# Ultra-Mega-PS-DAC-V1_00.net
KiCad netlist of a schematic drawn in Altium Designer
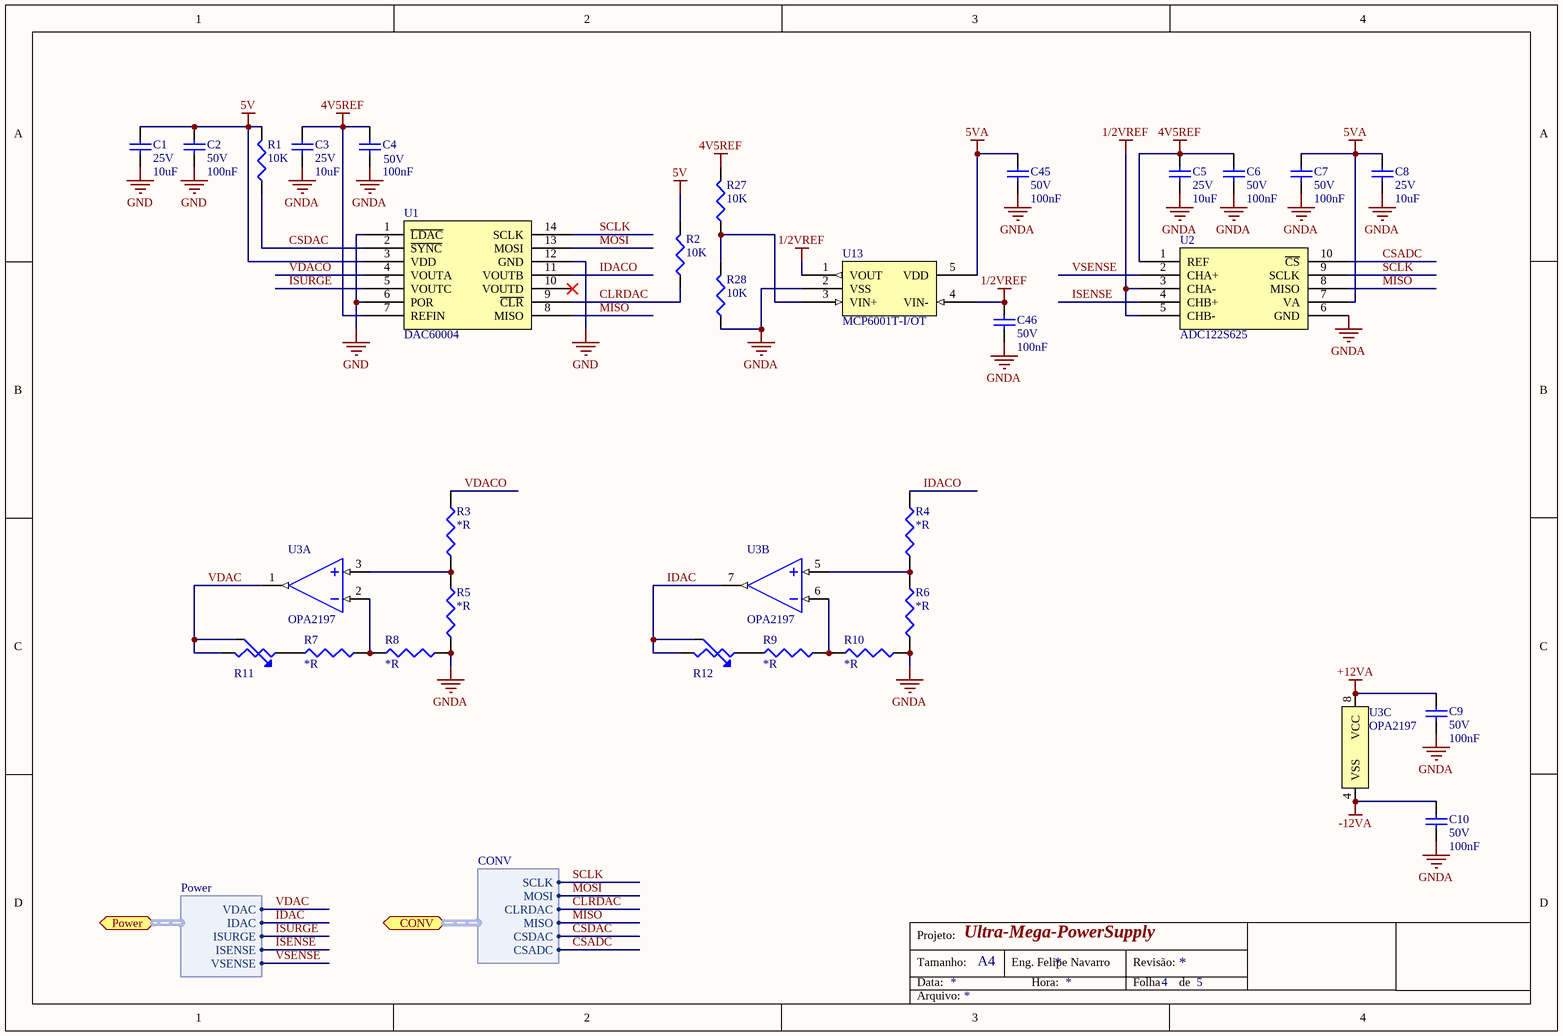
[diagram p0: Ultra-Mega-PS-DAC-V1.00.SchDoc]

(export (version "E")
  (design (tool "Eeschema 10.0.6"))
  (components
    (comp (ref "C1")
      (value "10uF")
      (footprint "CC0805")
      (description "Capacitor (Semiconductor SIM Model)")
      (fields (field (name "TENSÃO") "25V") (field (name "Comment") "Capacitor Cerâmico"))
      (libsource (lib "NavarroCAP") (part "Cap 10uF 25V 0805 X5R"))
    )
    (comp (ref "C2")
      (value "100nF")
      (footprint "CC0603")
      (description "Capacitor (Semiconductor SIM Model)")
      (fields (field (name "TENSÃO") "50V") (field (name "Comment") "Capacitor Cerâmico"))
      (libsource (lib "NavarroCAP") (part "Cap 100nF 50V 0603 X7R"))
    )
    (comp (ref "C3")
      (value "10uF")
      (footprint "CC0805")
      (description "Capacitor (Semiconductor SIM Model)")
      (fields (field (name "TENSÃO") "25V") (field (name "Comment") "Capacitor Cerâmico"))
      (libsource (lib "NavarroCAP") (part "Cap 10uF 25V 0805 X5R"))
    )
    (comp (ref "C4")
      (value "100nF")
      (footprint "CC0603")
      (description "Capacitor (Semiconductor SIM Model)")
      (fields (field (name "TENSÃO") "50V") (field (name "Comment") "Capacitor Cerâmico"))
      (libsource (lib "NavarroCAP") (part "Cap 100nF 50V 0603 X7R"))
    )
    (comp (ref "C5")
      (value "10uF")
      (footprint "CC0805")
      (description "Capacitor (Semiconductor SIM Model)")
      (fields (field (name "TENSÃO") "25V") (field (name "Comment") "Capacitor Cerâmico"))
      (libsource (lib "NavarroCAP") (part "Cap 10uF 25V 0805 X5R"))
    )
    (comp (ref "C6")
      (value "100nF")
      (footprint "CC0603")
      (description "Capacitor (Semiconductor SIM Model)")
      (fields (field (name "TENSÃO") "50V") (field (name "Comment") "Capacitor Cerâmico"))
      (libsource (lib "NavarroCAP") (part "Cap 100nF 50V 0603 X7R"))
    )
    (comp (ref "C7")
      (value "100nF")
      (footprint "CC0603")
      (description "Capacitor (Semiconductor SIM Model)")
      (fields (field (name "TENSÃO") "50V") (field (name "Comment") "Capacitor Cerâmico"))
      (libsource (lib "NavarroCAP") (part "Cap 100nF 50V 0603 X7R"))
    )
    (comp (ref "C8")
      (value "10uF")
      (footprint "CC0805")
      (description "Capacitor (Semiconductor SIM Model)")
      (fields (field (name "TENSÃO") "25V") (field (name "Comment") "Capacitor Cerâmico"))
      (libsource (lib "NavarroCAP") (part "Cap 10uF 25V 0805 X5R"))
    )
    (comp (ref "C9")
      (value "100nF")
      (footprint "CC0603")
      (description "Capacitor (Semiconductor SIM Model)")
      (fields (field (name "TENSÃO") "50V") (field (name "Comment") "Capacitor Cerâmico"))
      (libsource (lib "NavarroCAP") (part "Cap 100nF 50V 0603 X7R"))
    )
    (comp (ref "C10")
      (value "100nF")
      (footprint "CC0603")
      (description "Capacitor (Semiconductor SIM Model)")
      (fields (field (name "TENSÃO") "50V") (field (name "Comment") "Capacitor Cerâmico"))
      (libsource (lib "NavarroCAP") (part "Cap 100nF 50V 0603 X7R"))
    )
    (comp (ref "C45")
      (value "100nF")
      (footprint "CC0603")
      (description "Capacitor (Semiconductor SIM Model)")
      (fields (field (name "TENSÃO") "50V") (field (name "Comment") "Capacitor Cerâmico"))
      (libsource (lib "NavarroCAP") (part "Cap 100nF 50V 0603 X7R"))
    )
    (comp (ref "C46")
      (value "100nF")
      (footprint "CC0603")
      (description "Capacitor (Semiconductor SIM Model)")
      (fields (field (name "TENSÃO") "50V") (field (name "Comment") "Capacitor Cerâmico"))
      (libsource (lib "NavarroCAP") (part "Cap 100nF 50V 0603 X7R"))
    )
    (comp (ref "R1")
      (value "10K")
      (footprint "CC0603")
      (description "Resistor")
      (libsource (lib "NavarroRES") (part "Res 10K 1% 0603 1/10W"))
    )
    (comp (ref "R2")
      (value "10K")
      (footprint "CC0603")
      (description "Resistor")
      (libsource (lib "NavarroRES") (part "Res 10K 1% 0603 1/10W"))
    )
    (comp (ref "R3")
      (value "*R")
      (footprint "CC0603")
      (description "Resistor")
      (libsource (lib "NavarroRES") (part "Res - $Val $% $Footprint $Pot"))
    )
    (comp (ref "R4")
      (value "*R")
      (footprint "CC0603")
      (description "Resistor")
      (libsource (lib "NavarroRES") (part "Res - $Val $% $Footprint $Pot"))
    )
    (comp (ref "R5")
      (value "*R")
      (footprint "CC0603")
      (description "Resistor")
      (libsource (lib "NavarroRES") (part "Res - $Val $% $Footprint $Pot"))
    )
    (comp (ref "R6")
      (value "*R")
      (footprint "CC0603")
      (description "Resistor")
      (libsource (lib "NavarroRES") (part "Res - $Val $% $Footprint $Pot"))
    )
    (comp (ref "R7")
      (value "*R")
      (footprint "CC0603")
      (description "Resistor")
      (libsource (lib "NavarroRES") (part "Res - $Val $% $Footprint $Pot"))
    )
    (comp (ref "R8")
      (value "*R")
      (footprint "CC0603")
      (description "Resistor")
      (libsource (lib "NavarroRES") (part "Res - $Val $% $Footprint $Pot"))
    )
    (comp (ref "R9")
      (value "*R")
      (footprint "CC0603")
      (description "Resistor")
      (libsource (lib "NavarroRES") (part "Res - $Val $% $Footprint $Pot"))
    )
    (comp (ref "R10")
      (value "*R")
      (footprint "CC0603")
      (description "Resistor")
      (libsource (lib "NavarroRES") (part "Res - $Val $% $Footprint $Pot"))
    )
    (comp (ref "R11")
      (value "Potenciômetro")
      (footprint "POT")
      (description "Trimmer")
      (libsource (lib "NavarroRES") (part "Res Trim"))
    )
    (comp (ref "R12")
      (value "Potenciômetro")
      (footprint "POT")
      (description "Trimmer")
      (libsource (lib "NavarroRES") (part "Res Trim"))
    )
    (comp (ref "R27")
      (value "10K")
      (footprint "CC0603")
      (description "Resistor")
      (libsource (lib "NavarroRES") (part "Res 10K 1% 0603 1/10W"))
    )
    (comp (ref "R28")
      (value "10K")
      (footprint "CC0603")
      (description "Resistor")
      (libsource (lib "NavarroRES") (part "Res 10K 1% 0603 1/10W"))
    )
    (comp (ref "U1")
      (value "DAC60004")
      (footprint "TSSOP-14N")
      (description "DACx0004, Quad 16-,14-,12-Bit, 1 LSB INL, Buffered, Voltage-Output Digital-to-Analog  Converters")
      (libsource (lib "Navarro") (part "DAC6004"))
    )
    (comp (ref "U2")
      (value "ADC122S625")
      (footprint "MSOP10")
      (description "ADC122S625 Dual 12-Bit, 50 kSPS to 200 kSPS, Simultaneous Sampling A/D Converter")
      (libsource (lib "Navarro") (part "ADC122S625"))
    )
    (comp (ref "U3")
      (value "OPA2197")
      (footprint "SOIC-8N")
      (description "OPAx197 36-V, Precision, Rail-to-Rail Input/Output, Low Offset Voltage, Operational Amplifiers")
      (libsource (lib "") (part "OPA2197_1"))
    )
    (comp (ref "U13")
      (value "MCP6001T-I/OT")
      (footprint "SOT-23-5N")
      (description "1 MHz, Low-Power Op Amp")
      (libsource (lib "Navarro") (part "MCP6001"))
    )
  )
  (nets
    (net (code "3") (name "+12VA") (class "Default")
      (node (ref "C9") (pin "2") (pinfunction "2_2") (pintype "passive"))
      (node (ref "U3") (pin "8") (pinfunction "VCC_8") (pintype "power_in"))
    )
    (net (code "4") (name "-12VA") (class "Default")
      (node (ref "C10") (pin "2") (pinfunction "2_2") (pintype "passive"))
      (node (ref "U3") (pin "4") (pinfunction "VSS_4") (pintype "power_in"))
    )
    (net (code "5") (name "/CLRDAC") (class "Default")
      (node (ref "R2") (pin "1") (pinfunction "1_1") (pintype "passive"))
      (node (ref "U1") (pin "9") (pinfunction "~{CLR}_9") (pintype "passive"))
    )
    (net (code "6") (name "/CSADC") (class "Default")
      (node (ref "U2") (pin "10") (pinfunction "~{CS}_10") (pintype "passive"))
    )
    (net (code "7") (name "/CSDAC") (class "Default")
      (node (ref "R1") (pin "1") (pinfunction "1_1") (pintype "passive"))
      (node (ref "U1") (pin "2") (pinfunction "~{SYNC}_2") (pintype "passive"))
    )
    (net (code "8") (name "/IDAC") (class "Default")
      (node (ref "R12") (pin "2") (pinfunction "TAP_2") (pintype "passive"))
      (node (ref "R12") (pin "3") (pinfunction "3_3") (pintype "passive"))
      (node (ref "U3") (pin "7") (pinfunction "OUTB_7") (pintype "output"))
    )
    (net (code "9") (name "/IDACO") (class "Default")
      (node (ref "R4") (pin "2") (pinfunction "2_2") (pintype "passive"))
      (node (ref "U1") (pin "11") (pinfunction "VOUTB_11") (pintype "passive"))
    )
    (net (code "10") (name "/ISENSE") (class "Default")
      (node (ref "U2") (pin "4") (pinfunction "CHB+_4") (pintype "power_in"))
    )
    (net (code "11") (name "/ISURGE") (class "Default")
      (node (ref "U1") (pin "5") (pinfunction "VOUTC_5") (pintype "passive"))
    )
    (net (code "12") (name "/MISO") (class "Default")
      (node (ref "U1") (pin "8") (pinfunction "MISO_8") (pintype "passive"))
      (node (ref "U2") (pin "8") (pinfunction "MISO_8") (pintype "passive"))
    )
    (net (code "13") (name "/MOSI") (class "Default")
      (node (ref "U1") (pin "13") (pinfunction "MOSI_13") (pintype "passive"))
    )
    (net (code "14") (name "/SCLK") (class "Default")
      (node (ref "U1") (pin "14") (pinfunction "SCLK_14") (pintype "passive"))
      (node (ref "U2") (pin "9") (pinfunction "SCLK_9") (pintype "passive"))
    )
    (net (code "15") (name "/VDAC") (class "Default")
      (node (ref "R11") (pin "2") (pinfunction "TAP_2") (pintype "passive"))
      (node (ref "R11") (pin "3") (pinfunction "3_3") (pintype "passive"))
      (node (ref "U3") (pin "1") (pinfunction "OUTA_1") (pintype "output"))
    )
    (net (code "16") (name "/VDACO") (class "Default")
      (node (ref "R3") (pin "2") (pinfunction "2_2") (pintype "passive"))
      (node (ref "U1") (pin "4") (pinfunction "VOUTA_4") (pintype "passive"))
    )
    (net (code "17") (name "/VSENSE") (class "Default")
      (node (ref "U2") (pin "2") (pinfunction "CHA+_2") (pintype "passive"))
    )
    (net (code "20") (name "1{slash}2VREF") (class "Default")
      (node (ref "C46") (pin "2") (pinfunction "2_2") (pintype "passive"))
      (node (ref "U13") (pin "1") (pinfunction "VOUT_1") (pintype "output"))
      (node (ref "U13") (pin "4") (pinfunction "VIN-_4") (pintype "input"))
      (node (ref "U2") (pin "3") (pinfunction "CHA-_3") (pintype "passive"))
      (node (ref "U2") (pin "5") (pinfunction "CHB-_5") (pintype "power_in"))
    )
    (net (code "21") (name "4V5REF") (class "Default")
      (node (ref "C3") (pin "2") (pinfunction "2_2") (pintype "passive"))
      (node (ref "C4") (pin "2") (pinfunction "2_2") (pintype "passive"))
      (node (ref "C5") (pin "2") (pinfunction "2_2") (pintype "passive"))
      (node (ref "C6") (pin "2") (pinfunction "2_2") (pintype "passive"))
      (node (ref "R27") (pin "2") (pinfunction "2_2") (pintype "passive"))
      (node (ref "U1") (pin "7") (pinfunction "REFIN_7") (pintype "passive"))
      (node (ref "U2") (pin "1") (pinfunction "REF_1") (pintype "passive"))
    )
    (net (code "22") (name "5V") (class "Default")
      (node (ref "C1") (pin "2") (pinfunction "2_2") (pintype "passive"))
      (node (ref "C2") (pin "2") (pinfunction "2_2") (pintype "passive"))
      (node (ref "R1") (pin "2") (pinfunction "2_2") (pintype "passive"))
      (node (ref "R2") (pin "2") (pinfunction "2_2") (pintype "passive"))
      (node (ref "U1") (pin "3") (pinfunction "VDD_3") (pintype "power_in"))
    )
    (net (code "23") (name "5VA") (class "Default")
      (node (ref "C45") (pin "2") (pinfunction "2_2") (pintype "passive"))
      (node (ref "C7") (pin "2") (pinfunction "2_2") (pintype "passive"))
      (node (ref "C8") (pin "2") (pinfunction "2_2") (pintype "passive"))
      (node (ref "U13") (pin "5") (pinfunction "VDD_5") (pintype "power_in"))
      (node (ref "U2") (pin "7") (pinfunction "VA_7") (pintype "passive"))
    )
    (net (code "24") (name "GND") (class "Default")
      (node (ref "C1") (pin "1") (pinfunction "1_1") (pintype "passive"))
      (node (ref "C2") (pin "1") (pinfunction "1_1") (pintype "passive"))
      (node (ref "U1") (pin "1") (pinfunction "~{LDAC}_1") (pintype "passive"))
      (node (ref "U1") (pin "12") (pinfunction "GND_12") (pintype "power_in"))
      (node (ref "U1") (pin "6") (pinfunction "POR_6") (pintype "passive"))
    )
    (net (code "25") (name "GNDA") (class "Default")
      (node (ref "C10") (pin "1") (pinfunction "1_1") (pintype "passive"))
      (node (ref "C3") (pin "1") (pinfunction "1_1") (pintype "passive"))
      (node (ref "C4") (pin "1") (pinfunction "1_1") (pintype "passive"))
      (node (ref "C45") (pin "1") (pinfunction "1_1") (pintype "passive"))
      (node (ref "C46") (pin "1") (pinfunction "1_1") (pintype "passive"))
      (node (ref "C5") (pin "1") (pinfunction "1_1") (pintype "passive"))
      (node (ref "C6") (pin "1") (pinfunction "1_1") (pintype "passive"))
      (node (ref "C7") (pin "1") (pinfunction "1_1") (pintype "passive"))
      (node (ref "C8") (pin "1") (pinfunction "1_1") (pintype "passive"))
      (node (ref "C9") (pin "1") (pinfunction "1_1") (pintype "passive"))
      (node (ref "R10") (pin "2") (pinfunction "2_2") (pintype "passive"))
      (node (ref "R28") (pin "1") (pinfunction "1_1") (pintype "passive"))
      (node (ref "R5") (pin "1") (pinfunction "1_1") (pintype "passive"))
      (node (ref "R6") (pin "1") (pinfunction "1_1") (pintype "passive"))
      (node (ref "R8") (pin "2") (pinfunction "2_2") (pintype "passive"))
      (node (ref "U13") (pin "2") (pinfunction "VSS_2") (pintype "power_in"))
      (node (ref "U2") (pin "6") (pinfunction "GND_6") (pintype "passive"))
    )
    (net (code "26") (name "Net-(R11-Pad1)") (class "Default")
      (node (ref "R11") (pin "1") (pinfunction "1_1") (pintype "passive"))
      (node (ref "R7") (pin "1") (pinfunction "1_1") (pintype "passive"))
    )
    (net (code "27") (name "Net-(R12-Pad1)") (class "Default")
      (node (ref "R12") (pin "1") (pinfunction "1_1") (pintype "passive"))
      (node (ref "R9") (pin "1") (pinfunction "1_1") (pintype "passive"))
    )
    (net (code "28") (name "Net-(U3A-INA+)") (class "Default")
      (node (ref "R3") (pin "1") (pinfunction "1_1") (pintype "passive"))
      (node (ref "R5") (pin "2") (pinfunction "2_2") (pintype "passive"))
      (node (ref "U3") (pin "3") (pinfunction "INA+_3") (pintype "input"))
    )
    (net (code "29") (name "Net-(U3A-INA-)") (class "Default")
      (node (ref "R7") (pin "2") (pinfunction "2_2") (pintype "passive"))
      (node (ref "R8") (pin "1") (pinfunction "1_1") (pintype "passive"))
      (node (ref "U3") (pin "2") (pinfunction "INA-_2") (pintype "input"))
    )
    (net (code "30") (name "Net-(U3B-INB+)") (class "Default")
      (node (ref "R4") (pin "1") (pinfunction "1_1") (pintype "passive"))
      (node (ref "R6") (pin "2") (pinfunction "2_2") (pintype "passive"))
      (node (ref "U3") (pin "5") (pinfunction "INB+_5") (pintype "input"))
    )
    (net (code "31") (name "Net-(U3B-INB-)") (class "Default")
      (node (ref "R10") (pin "1") (pinfunction "1_1") (pintype "passive"))
      (node (ref "R9") (pin "2") (pinfunction "2_2") (pintype "passive"))
      (node (ref "U3") (pin "6") (pinfunction "INB-_6") (pintype "input"))
    )
    (net (code "32") (name "Net-(U13-VIN+)") (class "Default")
      (node (ref "R27") (pin "1") (pinfunction "1_1") (pintype "passive"))
      (node (ref "R28") (pin "2") (pinfunction "2_2") (pintype "passive"))
      (node (ref "U13") (pin "3") (pinfunction "VIN+_3") (pintype "input"))
    )
    (net (code "33") (name "unconnected-(U1-VOUTD-Pad10)") (class "Default")
      (node (ref "U1") (pin "10") (pinfunction "VOUTD_10") (pintype "passive+no_connect"))
    )
  )
)
